# ESP12_Dev_2Layer.net
KiCad netlist of a schematic drawn in EAGLE
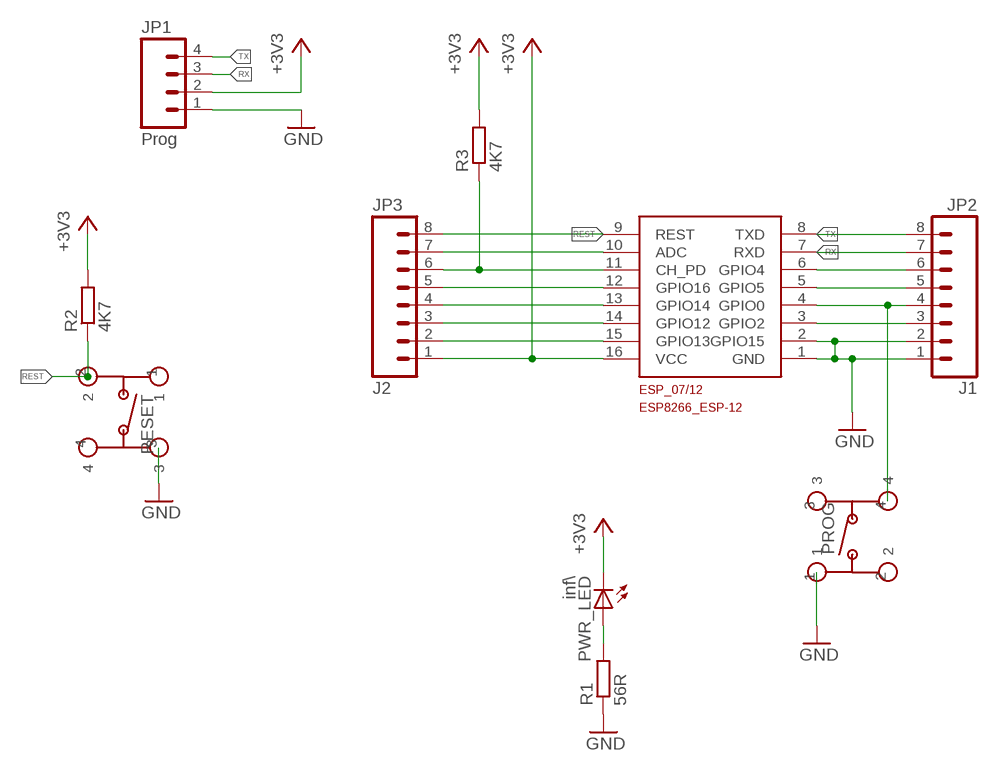
[diagram p0: schematic, sheet 1]

(export (version "E")
  (design (tool "Eeschema 10.0.6"))
  (components
    (comp (ref "ESP_07/12")
      (value "ESP8266_ESP-12")
      (footprint "eagle-import:ESP8266-ESP12")
      (libsource (lib "eagle-import") (part "ESP8266_ESP-12"))
    )
    (comp (ref "JP1")
      (value "Prog")
      (footprint "eagle-import:1X04_LOCK")
      (libsource (lib "eagle-import") (part "M04LOCK"))
    )
    (comp (ref "JP2")
      (value "J1")
      (footprint "eagle-import:1X08_LOCK")
      (libsource (lib "eagle-import") (part "M08LOCK"))
    )
    (comp (ref "JP3")
      (value "J2")
      (footprint "eagle-import:1X08_LOCK")
      (libsource (lib "eagle-import") (part "M08LOCK"))
    )
    (comp (ref "PROG")
      (value "TACTILE-SWITCH-SMD")
      (footprint "eagle-import:TACTILE-SWITCH-SMD")
      (libsource (lib "eagle-import") (part "TACTILE-SWITCH-SMD"))
    )
    (comp (ref "PWR_LED")
      (value "inf\\")
      (footprint "eagle-import:CHIPLED_0805")
      (libsource (lib "eagle-import") (part "LEDCHIPLED_0805"))
    )
    (comp (ref "R1")
      (value "56R")
      (footprint "eagle-import:R0805")
      (libsource (lib "eagle-import") (part "R-EU_R0805"))
    )
    (comp (ref "R2")
      (value "4K7")
      (footprint "eagle-import:R0805")
      (libsource (lib "eagle-import") (part "R-EU_R0805"))
    )
    (comp (ref "R3")
      (value "4K7")
      (footprint "eagle-import:R0805")
      (libsource (lib "eagle-import") (part "R-EU_R0805"))
    )
    (comp (ref "RESET")
      (value "TACTILE-SWITCH-SMD")
      (footprint "eagle-import:TACTILE-SWITCH-SMD")
      (libsource (lib "eagle-import") (part "TACTILE-SWITCH-SMD"))
    )
  )
  (nets
    (net (code "1") (name "+3V3") (class "Default")
      (node (ref "ESP_07/12") (pin "16") (pinfunction "VCC_16") (pintype "bidirectional"))
      (node (ref "JP1") (pin "2") (pinfunction "2_2") (pintype "passive"))
      (node (ref "JP3") (pin "1") (pinfunction "1_1") (pintype "passive"))
      (node (ref "PWR_LED") (pin "C") (pinfunction "C_C") (pintype "passive"))
      (node (ref "R2") (pin "2") (pinfunction "2_2") (pintype "passive"))
      (node (ref "R3") (pin "2") (pinfunction "2_2") (pintype "passive"))
    )
    (net (code "2") (name "GND") (class "Default")
      (node (ref "ESP_07/12") (pin "1") (pinfunction "GND_1") (pintype "bidirectional"))
      (node (ref "ESP_07/12") (pin "2") (pinfunction "GPIO15_2") (pintype "bidirectional"))
      (node (ref "JP1") (pin "1") (pinfunction "1_1") (pintype "passive"))
      (node (ref "JP2") (pin "1") (pinfunction "1_1") (pintype "passive"))
      (node (ref "JP2") (pin "2") (pinfunction "2_2") (pintype "passive"))
      (node (ref "PROG") (pin "1") (pinfunction "1_1") (pintype "bidirectional"))
      (node (ref "R1") (pin "1") (pinfunction "1_1") (pintype "passive"))
      (node (ref "RESET") (pin "3") (pinfunction "3_3") (pintype "bidirectional"))
    )
    (net (code "3") (name "Net-(ESP_07/12-ADC)") (class "Default")
      (node (ref "ESP_07/12") (pin "10") (pinfunction "ADC_10") (pintype "bidirectional"))
      (node (ref "JP3") (pin "7") (pinfunction "7_7") (pintype "passive"))
    )
    (net (code "4") (name "Net-(ESP_07/12-CH_PD)") (class "Default")
      (node (ref "ESP_07/12") (pin "11") (pinfunction "CH_PD_11") (pintype "bidirectional"))
      (node (ref "JP3") (pin "6") (pinfunction "6_6") (pintype "passive"))
      (node (ref "R3") (pin "1") (pinfunction "1_1") (pintype "passive"))
    )
    (net (code "5") (name "Net-(ESP_07/12-GPIO0)") (class "Default")
      (node (ref "ESP_07/12") (pin "4") (pinfunction "GPIO0_4") (pintype "bidirectional"))
      (node (ref "JP2") (pin "4") (pinfunction "4_4") (pintype "passive"))
      (node (ref "PROG") (pin "4") (pinfunction "4_4") (pintype "bidirectional"))
    )
    (net (code "6") (name "Net-(ESP_07/12-GPIO2)") (class "Default")
      (node (ref "ESP_07/12") (pin "3") (pinfunction "GPIO2_3") (pintype "bidirectional"))
      (node (ref "JP2") (pin "3") (pinfunction "3_3") (pintype "passive"))
    )
    (net (code "7") (name "Net-(ESP_07/12-GPIO4)") (class "Default")
      (node (ref "ESP_07/12") (pin "6") (pinfunction "GPIO4_6") (pintype "bidirectional"))
      (node (ref "JP2") (pin "6") (pinfunction "6_6") (pintype "passive"))
    )
    (net (code "8") (name "Net-(ESP_07/12-GPIO5)") (class "Default")
      (node (ref "ESP_07/12") (pin "5") (pinfunction "GPIO5_5") (pintype "bidirectional"))
      (node (ref "JP2") (pin "5") (pinfunction "5_5") (pintype "passive"))
    )
    (net (code "9") (name "Net-(ESP_07/12-GPIO12)") (class "Default")
      (node (ref "ESP_07/12") (pin "14") (pinfunction "GPIO12_14") (pintype "bidirectional"))
      (node (ref "JP3") (pin "3") (pinfunction "3_3") (pintype "passive"))
    )
    (net (code "10") (name "Net-(ESP_07/12-GPIO13)") (class "Default")
      (node (ref "ESP_07/12") (pin "15") (pinfunction "GPIO13_15") (pintype "bidirectional"))
      (node (ref "JP3") (pin "2") (pinfunction "2_2") (pintype "passive"))
    )
    (net (code "11") (name "Net-(ESP_07/12-GPIO14)") (class "Default")
      (node (ref "ESP_07/12") (pin "13") (pinfunction "GPIO14_13") (pintype "bidirectional"))
      (node (ref "JP3") (pin "4") (pinfunction "4_4") (pintype "passive"))
    )
    (net (code "12") (name "Net-(ESP_07/12-GPIO16)") (class "Default")
      (node (ref "ESP_07/12") (pin "12") (pinfunction "GPIO16_12") (pintype "bidirectional"))
      (node (ref "JP3") (pin "5") (pinfunction "5_5") (pintype "passive"))
    )
    (net (code "13") (name "Net-(PWR_LED-PadA)") (class "Default")
      (node (ref "PWR_LED") (pin "A") (pinfunction "A_A") (pintype "passive"))
      (node (ref "R1") (pin "2") (pinfunction "2_2") (pintype "passive"))
    )
    (net (code "14") (name "REST") (class "Default")
      (node (ref "ESP_07/12") (pin "9") (pinfunction "REST_9") (pintype "bidirectional"))
      (node (ref "JP3") (pin "8") (pinfunction "8_8") (pintype "passive"))
      (node (ref "R2") (pin "1") (pinfunction "1_1") (pintype "passive"))
      (node (ref "RESET") (pin "2") (pinfunction "2_2") (pintype "bidirectional"))
    )
    (net (code "15") (name "RX") (class "Default")
      (node (ref "ESP_07/12") (pin "7") (pinfunction "RXD_7") (pintype "bidirectional"))
      (node (ref "JP1") (pin "3") (pinfunction "3_3") (pintype "passive"))
      (node (ref "JP2") (pin "7") (pinfunction "7_7") (pintype "passive"))
    )
    (net (code "16") (name "TX") (class "Default")
      (node (ref "ESP_07/12") (pin "8") (pinfunction "TXD_8") (pintype "bidirectional"))
      (node (ref "JP1") (pin "4") (pinfunction "4_4") (pintype "passive"))
      (node (ref "JP2") (pin "8") (pinfunction "8_8") (pintype "passive"))
    )
    (net (code "17") (name "unconnected-(PROG-Pad2)") (class "Default")
      (node (ref "PROG") (pin "2") (pinfunction "2_2") (pintype "bidirectional"))
    )
    (net (code "18") (name "unconnected-(PROG-Pad3)") (class "Default")
      (node (ref "PROG") (pin "3") (pinfunction "3_3") (pintype "bidirectional"))
    )
    (net (code "19") (name "unconnected-(RESET-Pad1)") (class "Default")
      (node (ref "RESET") (pin "1") (pinfunction "1_1") (pintype "bidirectional"))
    )
    (net (code "20") (name "unconnected-(RESET-Pad4)") (class "Default")
      (node (ref "RESET") (pin "4") (pinfunction "4_4") (pintype "bidirectional"))
    )
  )
)
